# zamek.net
KiCad netlist of a schematic drawn in EAGLE
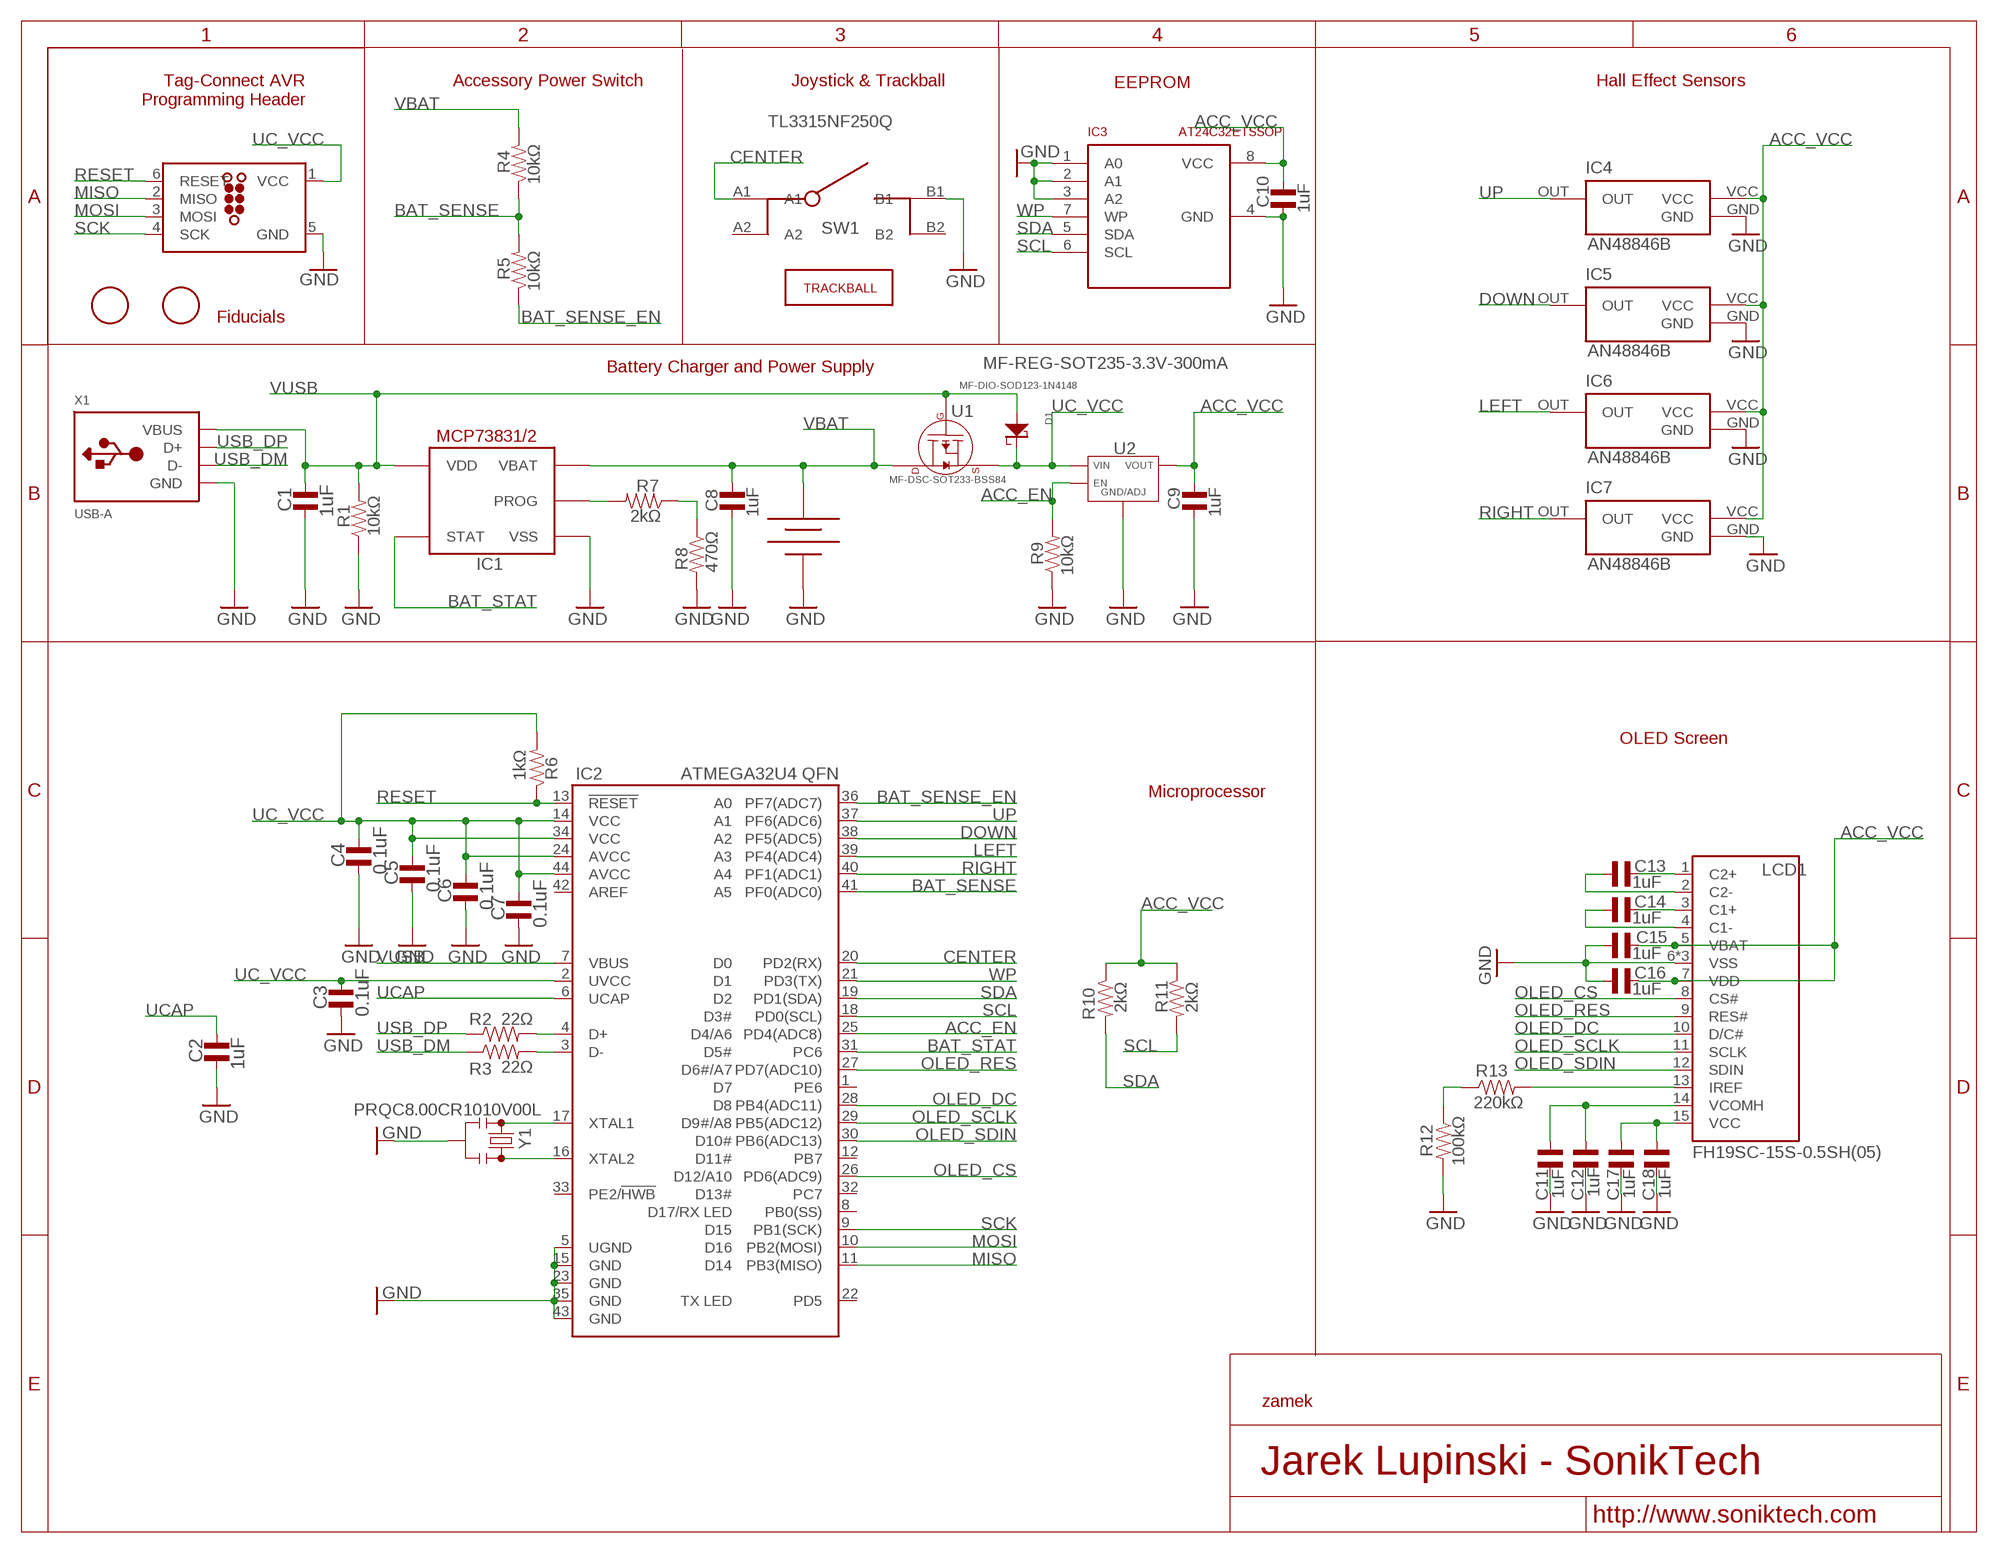
[diagram p0: schematic, sheet 1]

(export (version "E")
  (design (tool "Eeschema 10.0.6"))
  (components
    (comp (ref "BAT1")
      (value "LIPO201030")
      (footprint "eagle-import:201030LIPO")
      (libsource (lib "eagle-import") (part "LIPO201030"))
    )
    (comp (ref "C1")
      (value "1uF")
      (footprint "eagle-import:C0402")
      (libsource (lib "eagle-import") (part "CAPACITOR_NP_0402"))
    )
    (comp (ref "C2")
      (value "1uF")
      (footprint "eagle-import:C0402")
      (libsource (lib "eagle-import") (part "CAPACITOR_NP_0402"))
    )
    (comp (ref "C3")
      (value "0.1uF")
      (footprint "eagle-import:C0402")
      (libsource (lib "eagle-import") (part "CAPACITOR_NP_0402"))
    )
    (comp (ref "C4")
      (value "0.1uF")
      (footprint "eagle-import:C0402")
      (libsource (lib "eagle-import") (part "CAPACITOR_NP_0402"))
    )
    (comp (ref "C5")
      (value "0.1uF")
      (footprint "eagle-import:C0402")
      (libsource (lib "eagle-import") (part "CAPACITOR_NP_0402"))
    )
    (comp (ref "C6")
      (value "0.1uF")
      (footprint "eagle-import:C0402")
      (libsource (lib "eagle-import") (part "CAPACITOR_NP_0402"))
    )
    (comp (ref "C7")
      (value "0.1uF")
      (footprint "eagle-import:C0402")
      (libsource (lib "eagle-import") (part "CAPACITOR_NP_0402"))
    )
    (comp (ref "C8")
      (value "1uF")
      (footprint "eagle-import:C0402")
      (libsource (lib "eagle-import") (part "CAPACITOR_NP_0402"))
    )
    (comp (ref "C9")
      (value "1uF")
      (footprint "eagle-import:C0402")
      (libsource (lib "eagle-import") (part "CAPACITOR_NP_0402"))
    )
    (comp (ref "C10")
      (value "1uF")
      (footprint "eagle-import:C0402")
      (libsource (lib "eagle-import") (part "CAPACITOR_NP_0402"))
    )
    (comp (ref "C11")
      (value "1uF")
      (footprint "eagle-import:C0402")
      (libsource (lib "eagle-import") (part "CAPACITOR_NP_0402"))
    )
    (comp (ref "C12")
      (value "1uF")
      (footprint "eagle-import:C0402")
      (libsource (lib "eagle-import") (part "CAPACITOR_NP_0402"))
    )
    (comp (ref "C13")
      (value "1uF")
      (footprint "eagle-import:C0402")
      (libsource (lib "eagle-import") (part "CAPACITOR_NP_0402"))
    )
    (comp (ref "C14")
      (value "1uF")
      (footprint "eagle-import:C0402")
      (libsource (lib "eagle-import") (part "CAPACITOR_NP_0402"))
    )
    (comp (ref "C15")
      (value "1uF")
      (footprint "eagle-import:C0402")
      (libsource (lib "eagle-import") (part "CAPACITOR_NP_0402"))
    )
    (comp (ref "C16")
      (value "1uF")
      (footprint "eagle-import:C0402")
      (libsource (lib "eagle-import") (part "CAPACITOR_NP_0402"))
    )
    (comp (ref "C17")
      (value "1uF")
      (footprint "eagle-import:C0402")
      (libsource (lib "eagle-import") (part "CAPACITOR_NP_0402"))
    )
    (comp (ref "C18")
      (value "1uF")
      (footprint "eagle-import:C0402")
      (libsource (lib "eagle-import") (part "CAPACITOR_NP_0402"))
    )
    (comp (ref "D1")
      (value "MF-DIO-SOD123-1N4148")
      (footprint "eagle-import:SOD-123")
      (fields (field (name "HOUSEPART") "NO"))
      (libsource (lib "eagle-import") (part "DIODES_SOD-123"))
    )
    (comp (ref "IC1")
      (value "MCP73831")
      (footprint "eagle-import:MFSOT23-5L")
      (libsource (lib "eagle-import") (part "MCP73831MF"))
    )
    (comp (ref "IC2")
      (value "ATMEGA32U4 QFN")
      (footprint "eagle-import:QFN-44-NOPAD")
      (libsource (lib "eagle-import") (part "ATMEGA32U4QFN2"))
    )
    (comp (ref "IC3")
      (value "AT24C32ETSSOP")
      (footprint "eagle-import:TSSOP8-W")
      (libsource (lib "eagle-import") (part "AT24C32ETSSOP"))
    )
    (comp (ref "IC4")
      (value "AN48846B")
      (footprint "eagle-import:HALLSENSOR")
      (libsource (lib "eagle-import") (part "HALLSENSOR"))
    )
    (comp (ref "IC5")
      (value "AN48846B")
      (footprint "eagle-import:HALLSENSOR")
      (libsource (lib "eagle-import") (part "HALLSENSOR"))
    )
    (comp (ref "IC6")
      (value "AN48846B")
      (footprint "eagle-import:HALLSENSOR")
      (libsource (lib "eagle-import") (part "HALLSENSOR"))
    )
    (comp (ref "IC7")
      (value "AN48846B")
      (footprint "eagle-import:HALLSENSOR")
      (libsource (lib "eagle-import") (part "HALLSENSOR"))
    )
    (comp (ref "J1")
      (value "TC2030-MCP-NLFIX")
      (footprint "eagle-import:TC2030-MCP-NL")
      (libsource (lib "eagle-import") (part "TC2030-MCP-NLFIX"))
    )
    (comp (ref "LCD1")
      (value "FH19SC-15S-0.5SH(05)")
      (footprint "eagle-import:ER-OLED0.91-3WWFH19C")
      (libsource (lib "eagle-import") (part "MICROBUILDER_OLED_UG-2832HSWEG04"))
    )
    (comp (ref "R1")
      (value "10kΩ")
      (footprint "eagle-import:R0402")
      (libsource (lib "eagle-import") (part "RESISTOR_0402"))
    )
    (comp (ref "R2")
      (value "22Ω")
      (footprint "eagle-import:R0402")
      (libsource (lib "eagle-import") (part "RESISTOR_0402"))
    )
    (comp (ref "R3")
      (value "22Ω")
      (footprint "eagle-import:R0402")
      (libsource (lib "eagle-import") (part "RESISTOR_0402"))
    )
    (comp (ref "R4")
      (value "10kΩ")
      (footprint "eagle-import:R0402")
      (libsource (lib "eagle-import") (part "RESISTOR_0402"))
    )
    (comp (ref "R5")
      (value "10kΩ")
      (footprint "eagle-import:R0402")
      (libsource (lib "eagle-import") (part "RESISTOR_0402"))
    )
    (comp (ref "R6")
      (value "1kΩ")
      (footprint "eagle-import:R0402")
      (libsource (lib "eagle-import") (part "RESISTOR_0402"))
    )
    (comp (ref "R7")
      (value "2kΩ")
      (footprint "eagle-import:R0402")
      (libsource (lib "eagle-import") (part "RESISTOR_0402"))
    )
    (comp (ref "R8")
      (value "470Ω")
      (footprint "eagle-import:R0402")
      (libsource (lib "eagle-import") (part "RESISTOR_0402"))
    )
    (comp (ref "R9")
      (value "10kΩ")
      (footprint "eagle-import:R0402")
      (libsource (lib "eagle-import") (part "RESISTOR_0402"))
    )
    (comp (ref "R10")
      (value "2kΩ")
      (footprint "eagle-import:R0402")
      (libsource (lib "eagle-import") (part "RESISTOR_0402"))
    )
    (comp (ref "R11")
      (value "2kΩ")
      (footprint "eagle-import:R0402")
      (libsource (lib "eagle-import") (part "RESISTOR_0402"))
    )
    (comp (ref "R12")
      (value "100kΩ")
      (footprint "eagle-import:R0402")
      (libsource (lib "eagle-import") (part "RESISTOR_0402"))
    )
    (comp (ref "R13")
      (value "220kΩ")
      (footprint "eagle-import:R0402")
      (libsource (lib "eagle-import") (part "RESISTOR_0402"))
    )
    (comp (ref "SW1")
      (value "TL3315NF250Q")
      (footprint "eagle-import:TRACKBALLBUTTON")
      (libsource (lib "eagle-import") (part "TL3315NF250Q"))
    )
    (comp (ref "SW2")
      (value "TRACKBALLMECH")
      (footprint "eagle-import:TRACKBALL")
      (libsource (lib "eagle-import") (part "TRACKBALLMECH"))
    )
    (comp (ref "U$1")
      (value "FIDUCIAL")
      (footprint "eagle-import:FIDUCIAL_1MM")
      (libsource (lib "eagle-import") (part "FIDUCIAL"))
    )
    (comp (ref "U$2")
      (value "FIDUCIAL")
      (footprint "eagle-import:FIDUCIAL_1MM")
      (libsource (lib "eagle-import") (part "FIDUCIAL"))
    )
    (comp (ref "U1")
      (value "MF-DSC-SOT233-BSS84")
      (footprint "eagle-import:SOT-23-3")
      (fields (field (name "HOUSEPART") "NO"))
      (libsource (lib "eagle-import") (part "P-CHANNEL_FET_SOT-23-3"))
    )
    (comp (ref "U2")
      (value "MF-REG-SOT235-3.3V-300mA")
      (footprint "eagle-import:SOT-23-5")
      (fields (field (name "HOUSEPART") "YES") (field (name "MPN") "F-REG-SOT235-3.3V-300mA"))
      (libsource (lib "eagle-import") (part "TLV70233PDBVR"))
    )
    (comp (ref "X1")
      (value "USB-A")
      (footprint "eagle-import:MOLEX_480371000")
      (libsource (lib "eagle-import") (part "USB-A"))
    )
    (comp (ref "Y1")
      (value "PRQC8.00CR1010V00L")
      (footprint "eagle-import:RESONATOR-SMD")
      (libsource (lib "eagle-import") (part "RESONATOR8MHZ"))
    )
  )
  (nets
    (net (code "1") (name "/ACC_EN") (class "Default")
      (node (ref "IC2") (pin "25") (pinfunction "PD4(ADC8)_25") (pintype "bidirectional"))
      (node (ref "R9") (pin "P$2") (pinfunction "P$2_P$2") (pintype "passive"))
      (node (ref "U2") (pin "P$3") (pinfunction "EN_P$3") (pintype "bidirectional"))
    )
    (net (code "2") (name "/ACC_VCC") (class "Default")
      (node (ref "C10") (pin "P$1") (pinfunction "P$1_P$1") (pintype "passive"))
      (node (ref "C15") (pin "P$2") (pinfunction "P$2_P$2") (pintype "passive"))
      (node (ref "C16") (pin "P$1") (pinfunction "P$1_P$1") (pintype "passive"))
      (node (ref "C9") (pin "P$1") (pinfunction "P$1_P$1") (pintype "passive"))
      (node (ref "IC3") (pin "8") (pinfunction "VCC_8") (pintype "bidirectional"))
      (node (ref "IC4") (pin "VCC") (pinfunction "VCC_VCC") (pintype "bidirectional"))
      (node (ref "IC5") (pin "VCC") (pinfunction "VCC_VCC") (pintype "bidirectional"))
      (node (ref "IC6") (pin "VCC") (pinfunction "VCC_VCC") (pintype "bidirectional"))
      (node (ref "IC7") (pin "VCC") (pinfunction "VCC_VCC") (pintype "bidirectional"))
      (node (ref "LCD1") (pin "5") (pinfunction "VBAT_5") (pintype "bidirectional"))
      (node (ref "LCD1") (pin "7") (pinfunction "VDD_7") (pintype "bidirectional"))
      (node (ref "R10") (pin "P$1") (pinfunction "P$1_P$1") (pintype "passive"))
      (node (ref "R11") (pin "P$1") (pinfunction "P$1_P$1") (pintype "passive"))
      (node (ref "U2") (pin "P$5") (pinfunction "VOUT_P$5") (pintype "bidirectional"))
    )
    (net (code "3") (name "/BAT_SENSE") (class "Default")
      (node (ref "IC2") (pin "41") (pinfunction "PF0(ADC0)_41") (pintype "bidirectional"))
      (node (ref "R4") (pin "P$1") (pinfunction "P$1_P$1") (pintype "passive"))
      (node (ref "R5") (pin "P$2") (pinfunction "P$2_P$2") (pintype "passive"))
    )
    (net (code "4") (name "/BAT_SENSE_EN") (class "Default")
      (node (ref "IC2") (pin "36") (pinfunction "PF7(ADC7)_36") (pintype "bidirectional"))
      (node (ref "R5") (pin "P$1") (pinfunction "P$1_P$1") (pintype "passive"))
    )
    (net (code "5") (name "/BAT_STAT") (class "Default")
      (node (ref "IC1") (pin "P$1") (pinfunction "STAT_P$1") (pintype "output"))
      (node (ref "IC2") (pin "31") (pinfunction "PC6_31") (pintype "bidirectional"))
    )
    (net (code "6") (name "/CENTER") (class "Default")
      (node (ref "IC2") (pin "20") (pinfunction "PD2(RX)_20") (pintype "bidirectional"))
      (node (ref "SW1") (pin "A1") (pinfunction "A1_A1") (pintype "bidirectional"))
    )
    (net (code "7") (name "/DOWN") (class "Default")
      (node (ref "IC2") (pin "38") (pinfunction "PF5(ADC5)_38") (pintype "bidirectional"))
      (node (ref "IC5") (pin "OUT") (pinfunction "OUT_OUT") (pintype "bidirectional"))
    )
    (net (code "8") (name "/LEFT") (class "Default")
      (node (ref "IC2") (pin "39") (pinfunction "PF4(ADC4)_39") (pintype "bidirectional"))
      (node (ref "IC6") (pin "OUT") (pinfunction "OUT_OUT") (pintype "bidirectional"))
    )
    (net (code "9") (name "/MISO") (class "Default")
      (node (ref "IC2") (pin "11") (pinfunction "PB3(MISO)_11") (pintype "bidirectional"))
      (node (ref "J1") (pin "2") (pinfunction "MISO_2") (pintype "bidirectional"))
    )
    (net (code "10") (name "/MOSI") (class "Default")
      (node (ref "IC2") (pin "10") (pinfunction "PB2(MOSI)_10") (pintype "bidirectional"))
      (node (ref "J1") (pin "3") (pinfunction "MOSI_3") (pintype "bidirectional"))
    )
    (net (code "11") (name "/OLED_CS") (class "Default")
      (node (ref "IC2") (pin "26") (pinfunction "PD6(ADC9)_26") (pintype "bidirectional"))
      (node (ref "LCD1") (pin "8") (pinfunction "CS#_8") (pintype "bidirectional"))
    )
    (net (code "12") (name "/OLED_DC") (class "Default")
      (node (ref "IC2") (pin "28") (pinfunction "PB4(ADC11)_28") (pintype "bidirectional"))
      (node (ref "LCD1") (pin "10") (pinfunction "D/C#_10") (pintype "bidirectional"))
    )
    (net (code "13") (name "/OLED_RES") (class "Default")
      (node (ref "IC2") (pin "27") (pinfunction "PD7(ADC10)_27") (pintype "bidirectional"))
      (node (ref "LCD1") (pin "9") (pinfunction "RES#_9") (pintype "bidirectional"))
    )
    (net (code "14") (name "/OLED_SCLK") (class "Default")
      (node (ref "IC2") (pin "29") (pinfunction "PB5(ADC12)_29") (pintype "bidirectional"))
      (node (ref "LCD1") (pin "11") (pinfunction "SCLK_11") (pintype "bidirectional"))
    )
    (net (code "15") (name "/OLED_SDIN") (class "Default")
      (node (ref "IC2") (pin "30") (pinfunction "PB6(ADC13)_30") (pintype "bidirectional"))
      (node (ref "LCD1") (pin "12") (pinfunction "SDIN_12") (pintype "bidirectional"))
    )
    (net (code "16") (name "/RESET") (class "Default")
      (node (ref "IC2") (pin "13") (pinfunction "~{RESET}_13") (pintype "bidirectional"))
      (node (ref "J1") (pin "6") (pinfunction "RESET_6") (pintype "bidirectional"))
      (node (ref "R6") (pin "P$1") (pinfunction "P$1_P$1") (pintype "passive"))
    )
    (net (code "17") (name "/RIGHT") (class "Default")
      (node (ref "IC2") (pin "40") (pinfunction "PF1(ADC1)_40") (pintype "bidirectional"))
      (node (ref "IC7") (pin "OUT") (pinfunction "OUT_OUT") (pintype "bidirectional"))
    )
    (net (code "18") (name "/SCK") (class "Default")
      (node (ref "IC2") (pin "9") (pinfunction "PB1(SCK)_9") (pintype "bidirectional"))
      (node (ref "J1") (pin "4") (pinfunction "SCK_4") (pintype "bidirectional"))
    )
    (net (code "19") (name "/SCL") (class "Default")
      (node (ref "IC2") (pin "18") (pinfunction "PD0(SCL)_18") (pintype "bidirectional"))
      (node (ref "IC3") (pin "6") (pinfunction "SCL_6") (pintype "bidirectional"))
      (node (ref "R11") (pin "P$2") (pinfunction "P$2_P$2") (pintype "passive"))
    )
    (net (code "20") (name "/SDA") (class "Default")
      (node (ref "IC2") (pin "19") (pinfunction "PD1(SDA)_19") (pintype "bidirectional"))
      (node (ref "IC3") (pin "5") (pinfunction "SDA_5") (pintype "bidirectional"))
      (node (ref "R10") (pin "P$2") (pinfunction "P$2_P$2") (pintype "passive"))
    )
    (net (code "21") (name "/UCAP") (class "Default")
      (node (ref "C2") (pin "P$1") (pinfunction "P$1_P$1") (pintype "passive"))
      (node (ref "IC2") (pin "6") (pinfunction "UCAP_6") (pintype "bidirectional"))
    )
    (net (code "22") (name "/UC_VCC") (class "Default")
      (node (ref "C3") (pin "P$1") (pinfunction "P$1_P$1") (pintype "passive"))
      (node (ref "C4") (pin "P$1") (pinfunction "P$1_P$1") (pintype "passive"))
      (node (ref "C5") (pin "P$1") (pinfunction "P$1_P$1") (pintype "passive"))
      (node (ref "C6") (pin "P$1") (pinfunction "P$1_P$1") (pintype "passive"))
      (node (ref "C7") (pin "P$1") (pinfunction "P$1_P$1") (pintype "passive"))
      (node (ref "D1") (pin "CATHODE") (pinfunction "CATHODE_CATHODE") (pintype "bidirectional"))
      (node (ref "IC2") (pin "14") (pinfunction "VCC_14") (pintype "bidirectional"))
      (node (ref "IC2") (pin "2") (pinfunction "UVCC_2") (pintype "bidirectional"))
      (node (ref "IC2") (pin "24") (pinfunction "AVCC_24") (pintype "bidirectional"))
      (node (ref "IC2") (pin "34") (pinfunction "VCC_34") (pintype "bidirectional"))
      (node (ref "IC2") (pin "44") (pinfunction "AVCC_44") (pintype "bidirectional"))
      (node (ref "J1") (pin "1") (pinfunction "VCC_1") (pintype "power_in"))
      (node (ref "R6") (pin "P$2") (pinfunction "P$2_P$2") (pintype "passive"))
      (node (ref "U1") (pin "P$2") (pinfunction "SOURCE_P$2") (pintype "bidirectional"))
      (node (ref "U2") (pin "P$1") (pinfunction "VIN_P$1") (pintype "bidirectional"))
    )
    (net (code "23") (name "/UP") (class "Default")
      (node (ref "IC2") (pin "37") (pinfunction "PF6(ADC6)_37") (pintype "bidirectional"))
      (node (ref "IC4") (pin "OUT") (pinfunction "OUT_OUT") (pintype "bidirectional"))
    )
    (net (code "24") (name "/USB_DM") (class "Default")
      (node (ref "R3") (pin "P$1") (pinfunction "P$1_P$1") (pintype "passive"))
      (node (ref "X1") (pin "2") (pinfunction "D-_2") (pintype "bidirectional"))
    )
    (net (code "25") (name "/USB_DP") (class "Default")
      (node (ref "R2") (pin "P$1") (pinfunction "P$1_P$1") (pintype "passive"))
      (node (ref "X1") (pin "3") (pinfunction "D+_3") (pintype "bidirectional"))
    )
    (net (code "26") (name "/VBAT") (class "Default")
      (node (ref "BAT1") (pin "POS") (pinfunction "POS_POS") (pintype "bidirectional"))
      (node (ref "C8") (pin "P$1") (pinfunction "P$1_P$1") (pintype "passive"))
      (node (ref "IC1") (pin "P$3") (pinfunction "VBAT_P$3") (pintype "bidirectional"))
      (node (ref "R4") (pin "P$2") (pinfunction "P$2_P$2") (pintype "passive"))
      (node (ref "U1") (pin "P$3") (pinfunction "DRAIN_P$3") (pintype "bidirectional"))
    )
    (net (code "27") (name "/VUSB") (class "Default")
      (node (ref "C1") (pin "P$1") (pinfunction "P$1_P$1") (pintype "passive"))
      (node (ref "D1") (pin "ANODE") (pinfunction "ANODE_ANODE") (pintype "bidirectional"))
      (node (ref "IC1") (pin "P$4") (pinfunction "VDD_P$4") (pintype "power_in"))
      (node (ref "IC2") (pin "7") (pinfunction "VBUS_7") (pintype "bidirectional"))
      (node (ref "R1") (pin "P$2") (pinfunction "P$2_P$2") (pintype "passive"))
      (node (ref "U1") (pin "P$1") (pinfunction "GATE_P$1") (pintype "bidirectional"))
      (node (ref "X1") (pin "1") (pinfunction "VBUS_1") (pintype "power_in"))
    )
    (net (code "28") (name "/WP") (class "Default")
      (node (ref "IC2") (pin "21") (pinfunction "PD3(TX)_21") (pintype "bidirectional"))
      (node (ref "IC3") (pin "7") (pinfunction "WP_7") (pintype "bidirectional"))
    )
    (net (code "29") (name "GND") (class "Default")
      (node (ref "BAT1") (pin "NEG") (pinfunction "NEG_NEG") (pintype "bidirectional"))
      (node (ref "C1") (pin "P$2") (pinfunction "P$2_P$2") (pintype "passive"))
      (node (ref "C10") (pin "P$2") (pinfunction "P$2_P$2") (pintype "passive"))
      (node (ref "C11") (pin "P$2") (pinfunction "P$2_P$2") (pintype "passive"))
      (node (ref "C12") (pin "P$2") (pinfunction "P$2_P$2") (pintype "passive"))
      (node (ref "C15") (pin "P$1") (pinfunction "P$1_P$1") (pintype "passive"))
      (node (ref "C16") (pin "P$2") (pinfunction "P$2_P$2") (pintype "passive"))
      (node (ref "C17") (pin "P$2") (pinfunction "P$2_P$2") (pintype "passive"))
      (node (ref "C18") (pin "P$2") (pinfunction "P$2_P$2") (pintype "passive"))
      (node (ref "C2") (pin "P$2") (pinfunction "P$2_P$2") (pintype "passive"))
      (node (ref "C3") (pin "P$2") (pinfunction "P$2_P$2") (pintype "passive"))
      (node (ref "C4") (pin "P$2") (pinfunction "P$2_P$2") (pintype "passive"))
      (node (ref "C5") (pin "P$2") (pinfunction "P$2_P$2") (pintype "passive"))
      (node (ref "C6") (pin "P$2") (pinfunction "P$2_P$2") (pintype "passive"))
      (node (ref "C7") (pin "P$2") (pinfunction "P$2_P$2") (pintype "passive"))
      (node (ref "C8") (pin "P$2") (pinfunction "P$2_P$2") (pintype "passive"))
      (node (ref "C9") (pin "P$2") (pinfunction "P$2_P$2") (pintype "passive"))
      (node (ref "IC1") (pin "P$2") (pinfunction "VSS_P$2") (pintype "power_in"))
      (node (ref "IC2") (pin "15") (pinfunction "GND_15") (pintype "bidirectional"))
      (node (ref "IC2") (pin "23") (pinfunction "GND_23") (pintype "bidirectional"))
      (node (ref "IC2") (pin "35") (pinfunction "GND_35") (pintype "bidirectional"))
      (node (ref "IC2") (pin "43") (pinfunction "GND_43") (pintype "bidirectional"))
      (node (ref "IC2") (pin "5") (pinfunction "UGND_5") (pintype "bidirectional"))
      (node (ref "IC3") (pin "1") (pinfunction "A0_1") (pintype "bidirectional"))
      (node (ref "IC3") (pin "2") (pinfunction "A1_2") (pintype "bidirectional"))
      (node (ref "IC3") (pin "3") (pinfunction "A2_3") (pintype "bidirectional"))
      (node (ref "IC3") (pin "4") (pinfunction "GND_4") (pintype "bidirectional"))
      (node (ref "IC4") (pin "GND") (pinfunction "GND_GND") (pintype "bidirectional"))
      (node (ref "IC5") (pin "GND") (pinfunction "GND_GND") (pintype "bidirectional"))
      (node (ref "IC6") (pin "GND") (pinfunction "GND_GND") (pintype "bidirectional"))
      (node (ref "IC7") (pin "GND") (pinfunction "GND_GND") (pintype "bidirectional"))
      (node (ref "J1") (pin "5") (pinfunction "GND_5") (pintype "power_in"))
      (node (ref "LCD1") (pin "6") (pinfunction "VSS_6") (pintype "bidirectional"))
      (node (ref "LCD1") (pin "EP1") (pinfunction "VSS_EP1") (pintype "bidirectional"))
      (node (ref "LCD1") (pin "EP2") (pinfunction "VSS_EP2") (pintype "bidirectional"))
      (node (ref "R1") (pin "P$1") (pinfunction "P$1_P$1") (pintype "passive"))
      (node (ref "R12") (pin "P$2") (pinfunction "P$2_P$2") (pintype "passive"))
      (node (ref "R8") (pin "P$2") (pinfunction "P$2_P$2") (pintype "passive"))
      (node (ref "R9") (pin "P$1") (pinfunction "P$1_P$1") (pintype "passive"))
      (node (ref "SW1") (pin "B1") (pinfunction "B1_B1") (pintype "bidirectional"))
      (node (ref "U2") (pin "P$2") (pinfunction "GND/ADJ_P$2") (pintype "bidirectional"))
      (node (ref "U2") (pin "P$4") (pinfunction "GND/ADJ_P$4") (pintype "bidirectional"))
      (node (ref "X1") (pin "4") (pinfunction "GND_4") (pintype "power_in"))
      (node (ref "Y1") (pin "2") (pinfunction "2_2") (pintype "passive"))
    )
    (net (code "30") (name "Net-(IC1-PROG)") (class "Default")
      (node (ref "IC1") (pin "P$5") (pinfunction "PROG_P$5") (pintype "input"))
      (node (ref "R7") (pin "P$2") (pinfunction "P$2_P$2") (pintype "passive"))
    )
    (net (code "31") (name "Net-(IC2-D+)") (class "Default")
      (node (ref "IC2") (pin "4") (pinfunction "D+_4") (pintype "bidirectional"))
      (node (ref "R2") (pin "P$2") (pinfunction "P$2_P$2") (pintype "passive"))
    )
    (net (code "32") (name "Net-(IC2-D-)") (class "Default")
      (node (ref "IC2") (pin "3") (pinfunction "D-_3") (pintype "bidirectional"))
      (node (ref "R3") (pin "P$2") (pinfunction "P$2_P$2") (pintype "passive"))
    )
    (net (code "33") (name "Net-(IC2-XTAL1)") (class "Default")
      (node (ref "IC2") (pin "17") (pinfunction "XTAL1_17") (pintype "bidirectional"))
      (node (ref "Y1") (pin "1") (pinfunction "1_1") (pintype "passive"))
    )
    (net (code "34") (name "Net-(IC2-XTAL2)") (class "Default")
      (node (ref "IC2") (pin "16") (pinfunction "XTAL2_16") (pintype "bidirectional"))
      (node (ref "Y1") (pin "3") (pinfunction "3_3") (pintype "passive"))
    )
    (net (code "35") (name "Net-(LCD1-C1+)") (class "Default")
      (node (ref "C14") (pin "P$2") (pinfunction "P$2_P$2") (pintype "passive"))
      (node (ref "LCD1") (pin "3") (pinfunction "C1+_3") (pintype "bidirectional"))
    )
    (net (code "36") (name "Net-(LCD1-C1-)") (class "Default")
      (node (ref "C14") (pin "P$1") (pinfunction "P$1_P$1") (pintype "passive"))
      (node (ref "LCD1") (pin "4") (pinfunction "C1-_4") (pintype "bidirectional"))
    )
    (net (code "37") (name "Net-(LCD1-C2+)") (class "Default")
      (node (ref "C13") (pin "P$2") (pinfunction "P$2_P$2") (pintype "passive"))
      (node (ref "LCD1") (pin "1") (pinfunction "C2+_1") (pintype "bidirectional"))
    )
    (net (code "38") (name "Net-(LCD1-C2-)") (class "Default")
      (node (ref "C13") (pin "P$1") (pinfunction "P$1_P$1") (pintype "passive"))
      (node (ref "LCD1") (pin "2") (pinfunction "C2-_2") (pintype "bidirectional"))
    )
    (net (code "39") (name "Net-(LCD1-IREF)") (class "Default")
      (node (ref "LCD1") (pin "13") (pinfunction "IREF_13") (pintype "bidirectional"))
      (node (ref "R13") (pin "P$2") (pinfunction "P$2_P$2") (pintype "passive"))
    )
    (net (code "40") (name "Net-(LCD1-VCC)") (class "Default")
      (node (ref "C17") (pin "P$1") (pinfunction "P$1_P$1") (pintype "passive"))
      (node (ref "C18") (pin "P$1") (pinfunction "P$1_P$1") (pintype "passive"))
      (node (ref "LCD1") (pin "15") (pinfunction "VCC_15") (pintype "bidirectional"))
    )
    (net (code "41") (name "Net-(LCD1-VCOMH)") (class "Default")
      (node (ref "C11") (pin "P$1") (pinfunction "P$1_P$1") (pintype "passive"))
      (node (ref "C12") (pin "P$1") (pinfunction "P$1_P$1") (pintype "passive"))
      (node (ref "LCD1") (pin "14") (pinfunction "VCOMH_14") (pintype "bidirectional"))
    )
    (net (code "42") (name "Net-(R7-PadP$1)") (class "Default")
      (node (ref "R7") (pin "P$1") (pinfunction "P$1_P$1") (pintype "passive"))
      (node (ref "R8") (pin "P$1") (pinfunction "P$1_P$1") (pintype "passive"))
    )
    (net (code "43") (name "Net-(R12-PadP$1)") (class "Default")
      (node (ref "R12") (pin "P$1") (pinfunction "P$1_P$1") (pintype "passive"))
      (node (ref "R13") (pin "P$1") (pinfunction "P$1_P$1") (pintype "passive"))
    )
    (net (code "44") (name "unconnected-(IC2-AREF-Pad42)") (class "Default")
      (node (ref "IC2") (pin "42") (pinfunction "AREF_42") (pintype "bidirectional"))
    )
    (net (code "45") (name "unconnected-(IC2-PB0(SS)-Pad8)") (class "Default")
      (node (ref "IC2") (pin "8") (pinfunction "PB0(SS)_8") (pintype "bidirectional"))
    )
    (net (code "46") (name "unconnected-(IC2-PB7-Pad12)") (class "Default")
      (node (ref "IC2") (pin "12") (pinfunction "PB7_12") (pintype "bidirectional"))
    )
    (net (code "47") (name "unconnected-(IC2-PC7-Pad32)") (class "Default")
      (node (ref "IC2") (pin "32") (pinfunction "PC7_32") (pintype "bidirectional"))
    )
    (net (code "48") (name "unconnected-(IC2-PD5-Pad22)") (class "Default")
      (node (ref "IC2") (pin "22") (pinfunction "PD5_22") (pintype "bidirectional"))
    )
    (net (code "49") (name "unconnected-(IC2-PE2{slash}~{HWB}-Pad33)") (class "Default")
      (node (ref "IC2") (pin "33") (pinfunction "PE2/~{HWB}_33") (pintype "bidirectional"))
    )
    (net (code "50") (name "unconnected-(IC2-PE6-Pad1)") (class "Default")
      (node (ref "IC2") (pin "1") (pinfunction "PE6_1") (pintype "bidirectional"))
    )
    (net (code "51") (name "unconnected-(SW1-PadA2)") (class "Default")
      (node (ref "SW1") (pin "A2") (pinfunction "A2_A2") (pintype "bidirectional"))
    )
    (net (code "52") (name "unconnected-(SW1-PadB2)") (class "Default")
      (node (ref "SW1") (pin "B2") (pinfunction "B2_B2") (pintype "bidirectional"))
    )
  )
)
